# Adafruit_1_2in_7-segment.net
KiCad netlist of a schematic drawn in EAGLE
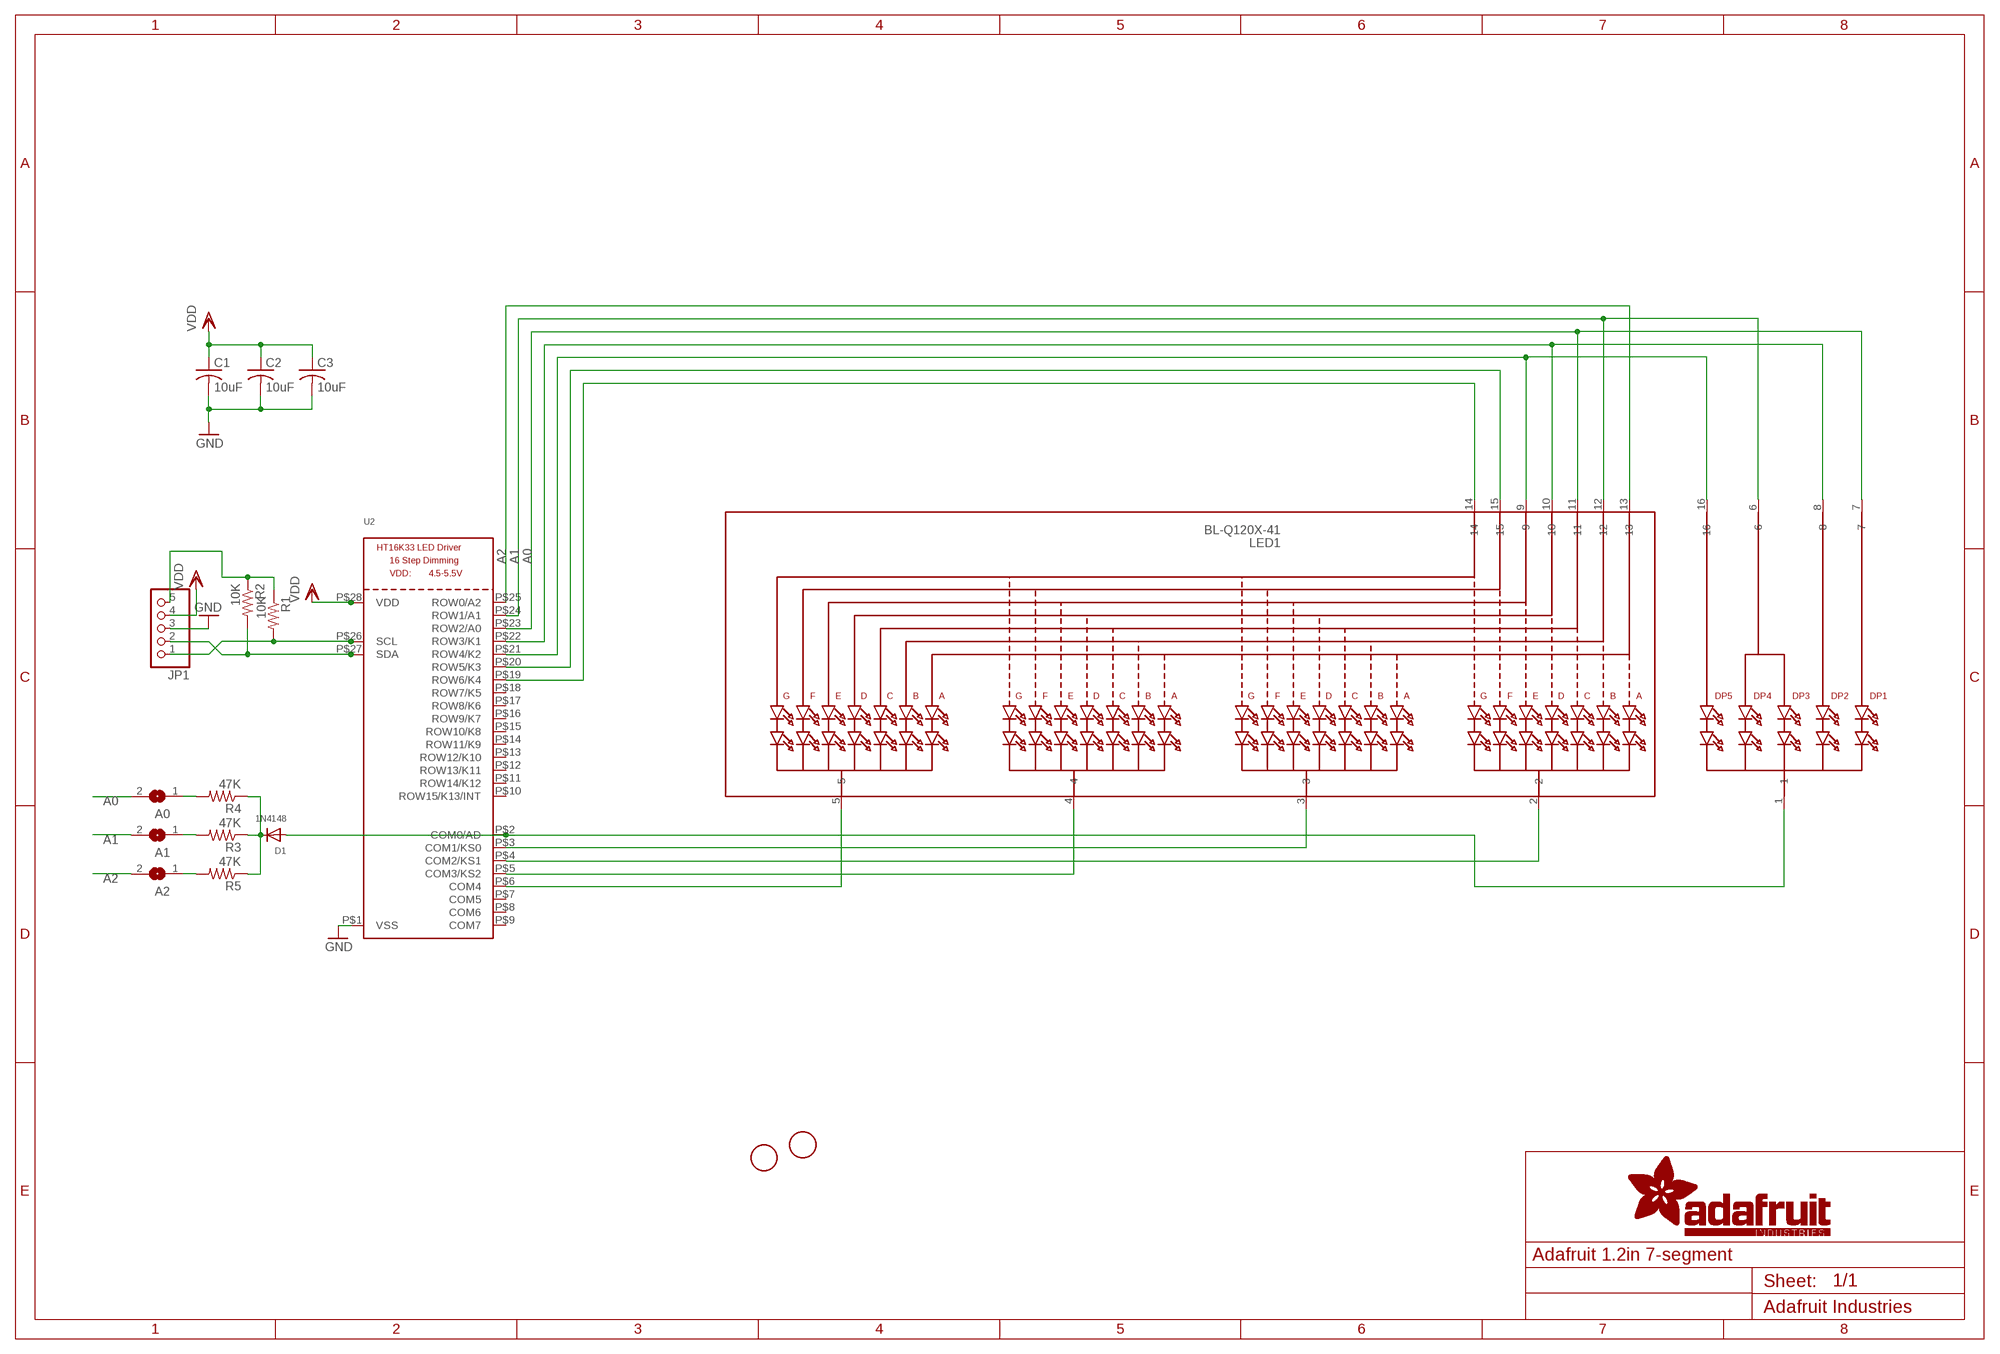
[diagram p0: schematic, sheet 1]

(export (version "E")
  (design (tool "Eeschema 10.0.6"))
  (components
    (comp (ref "A0")
      (value "SOLDERJUMPERREFLOW_NOPASTE")
      (footprint "eagle-import:SOLDERJUMPER_REFLOW_NOPASTE")
      (libsource (lib "eagle-import") (part "SOLDERJUMPERREFLOW_NOPASTE"))
    )
    (comp (ref "A1")
      (value "SOLDERJUMPERREFLOW_NOPASTE")
      (footprint "eagle-import:SOLDERJUMPER_REFLOW_NOPASTE")
      (libsource (lib "eagle-import") (part "SOLDERJUMPERREFLOW_NOPASTE"))
    )
    (comp (ref "A2")
      (value "SOLDERJUMPERREFLOW_NOPASTE")
      (footprint "eagle-import:SOLDERJUMPER_REFLOW_NOPASTE")
      (libsource (lib "eagle-import") (part "SOLDERJUMPERREFLOW_NOPASTE"))
    )
    (comp (ref "C1")
      (value "10uF")
      (footprint "eagle-import:C0805K")
      (libsource (lib "eagle-import") (part "C-USC0805K"))
    )
    (comp (ref "C2")
      (value "10uF")
      (footprint "eagle-import:C0805K")
      (libsource (lib "eagle-import") (part "C-USC0805K"))
    )
    (comp (ref "C3")
      (value "10uF")
      (footprint "eagle-import:C0805K")
      (libsource (lib "eagle-import") (part "C-USC0805K"))
    )
    (comp (ref "D1")
      (value "1N4148")
      (footprint "eagle-import:SOD-323F")
      (libsource (lib "eagle-import") (part "DIODESOD-323F"))
    )
    (comp (ref "JP1")
      (value "HEADER-1X576MIL")
      (footprint "eagle-import:1X05_ROUND_76")
      (libsource (lib "eagle-import") (part "HEADER-1X576MIL"))
    )
    (comp (ref "LED1")
      (value "BL-Q120X-41")
      (footprint "eagle-import:SEGMENT_BL-Q120A")
      (libsource (lib "eagle-import") (part "DISP_SEGMENT_4DIGIT_BL-Q120A"))
    )
    (comp (ref "R1")
      (value "10K")
      (footprint "eagle-import:R0805")
      (libsource (lib "eagle-import") (part "R-US_R0805"))
    )
    (comp (ref "R2")
      (value "10K")
      (footprint "eagle-import:R0805")
      (libsource (lib "eagle-import") (part "R-US_R0805"))
    )
    (comp (ref "R3")
      (value "47K")
      (footprint "eagle-import:R0805")
      (libsource (lib "eagle-import") (part "R-US_R0805"))
    )
    (comp (ref "R4")
      (value "47K")
      (footprint "eagle-import:R0805")
      (libsource (lib "eagle-import") (part "R-US_R0805"))
    )
    (comp (ref "R5")
      (value "47K")
      (footprint "eagle-import:R0805")
      (libsource (lib "eagle-import") (part "R-US_R0805"))
    )
    (comp (ref "U$1")
      (value "FIDUCIAL")
      (footprint "eagle-import:FIDUCIAL_1MM")
      (libsource (lib "eagle-import") (part "FIDUCIAL"))
    )
    (comp (ref "U$2")
      (value "FIDUCIAL")
      (footprint "eagle-import:FIDUCIAL_1MM")
      (libsource (lib "eagle-import") (part "FIDUCIAL"))
    )
    (comp (ref "U2")
      (value "HT16K33_SOP28")
      (footprint "eagle-import:SOP28_300MIL")
      (libsource (lib "eagle-import") (part "HT16K33_SOP28"))
    )
  )
  (nets
    (net (code "1") (name "/A0") (class "Default")
      (node (ref "A0") (pin "2") (pinfunction "2_2") (pintype "passive"))
      (node (ref "LED1") (pin "11") (pinfunction "11_11") (pintype "bidirectional"))
      (node (ref "LED1") (pin "7") (pinfunction "7_7") (pintype "bidirectional"))
      (node (ref "U2") (pin "P$23") (pinfunction "ROW2/A0_P$23") (pintype "bidirectional"))
    )
    (net (code "2") (name "/A1") (class "Default")
      (node (ref "A1") (pin "2") (pinfunction "2_2") (pintype "passive"))
      (node (ref "LED1") (pin "12") (pinfunction "12_12") (pintype "bidirectional"))
      (node (ref "LED1") (pin "6") (pinfunction "6_6") (pintype "bidirectional"))
      (node (ref "U2") (pin "P$24") (pinfunction "ROW1/A1_P$24") (pintype "bidirectional"))
    )
    (net (code "3") (name "/A2") (class "Default")
      (node (ref "A2") (pin "2") (pinfunction "2_2") (pintype "passive"))
      (node (ref "LED1") (pin "13") (pinfunction "13_13") (pintype "bidirectional"))
      (node (ref "U2") (pin "P$25") (pinfunction "ROW0/A2_P$25") (pintype "bidirectional"))
    )
    (net (code "4") (name "GND") (class "Default")
      (node (ref "C1") (pin "2") (pinfunction "2_2") (pintype "passive"))
      (node (ref "C2") (pin "2") (pinfunction "2_2") (pintype "passive"))
      (node (ref "C3") (pin "2") (pinfunction "2_2") (pintype "passive"))
      (node (ref "JP1") (pin "3") (pinfunction "3_3") (pintype "passive"))
      (node (ref "U2") (pin "P$1") (pinfunction "VSS_P$1") (pintype "bidirectional"))
    )
    (net (code "5") (name "Net-(A0-Pad1)") (class "Default")
      (node (ref "A0") (pin "1") (pinfunction "1_1") (pintype "passive"))
      (node (ref "R4") (pin "2") (pinfunction "2_2") (pintype "passive"))
    )
    (net (code "6") (name "Net-(A1-Pad1)") (class "Default")
      (node (ref "A1") (pin "1") (pinfunction "1_1") (pintype "passive"))
      (node (ref "R3") (pin "2") (pinfunction "2_2") (pintype "passive"))
    )
    (net (code "7") (name "Net-(A2-Pad1)") (class "Default")
      (node (ref "A2") (pin "1") (pinfunction "1_1") (pintype "passive"))
      (node (ref "R5") (pin "2") (pinfunction "2_2") (pintype "passive"))
    )
    (net (code "8") (name "Net-(D1-PadC)") (class "Default")
      (node (ref "D1") (pin "C") (pinfunction "C_C") (pintype "passive"))
      (node (ref "R3") (pin "1") (pinfunction "1_1") (pintype "passive"))
      (node (ref "R4") (pin "1") (pinfunction "1_1") (pintype "passive"))
      (node (ref "R5") (pin "1") (pinfunction "1_1") (pintype "passive"))
    )
    (net (code "9") (name "Net-(JP1-Pad5)") (class "Default")
      (node (ref "JP1") (pin "5") (pinfunction "5_5") (pintype "passive"))
      (node (ref "R1") (pin "1") (pinfunction "1_1") (pintype "passive"))
      (node (ref "R2") (pin "1") (pinfunction "1_1") (pintype "passive"))
    )
    (net (code "10") (name "Net-(U2-COM0{slash}AD)") (class "Default")
      (node (ref "D1") (pin "A") (pinfunction "A_A") (pintype "passive"))
      (node (ref "LED1") (pin "1") (pinfunction "1_1") (pintype "bidirectional"))
      (node (ref "U2") (pin "P$2") (pinfunction "COM0/AD_P$2") (pintype "bidirectional"))
    )
    (net (code "11") (name "Net-(U2-COM1{slash}KS0)") (class "Default")
      (node (ref "LED1") (pin "3") (pinfunction "3_3") (pintype "bidirectional"))
      (node (ref "U2") (pin "P$3") (pinfunction "COM1/KS0_P$3") (pintype "bidirectional"))
    )
    (net (code "12") (name "Net-(U2-COM2{slash}KS1)") (class "Default")
      (node (ref "LED1") (pin "2") (pinfunction "2_2") (pintype "bidirectional"))
      (node (ref "U2") (pin "P$4") (pinfunction "COM2/KS1_P$4") (pintype "bidirectional"))
    )
    (net (code "13") (name "Net-(U2-COM3{slash}KS2)") (class "Default")
      (node (ref "LED1") (pin "4") (pinfunction "4_4") (pintype "bidirectional"))
      (node (ref "U2") (pin "P$5") (pinfunction "COM3/KS2_P$5") (pintype "bidirectional"))
    )
    (net (code "14") (name "Net-(U2-COM4)") (class "Default")
      (node (ref "LED1") (pin "5") (pinfunction "5_5") (pintype "bidirectional"))
      (node (ref "U2") (pin "P$6") (pinfunction "COM4_P$6") (pintype "bidirectional"))
    )
    (net (code "15") (name "Net-(U2-ROW3{slash}K1)") (class "Default")
      (node (ref "LED1") (pin "10") (pinfunction "10_10") (pintype "bidirectional"))
      (node (ref "LED1") (pin "8") (pinfunction "8_8") (pintype "bidirectional"))
      (node (ref "U2") (pin "P$22") (pinfunction "ROW3/K1_P$22") (pintype "bidirectional"))
    )
    (net (code "16") (name "Net-(U2-ROW4{slash}K2)") (class "Default")
      (node (ref "LED1") (pin "16") (pinfunction "16_16") (pintype "bidirectional"))
      (node (ref "LED1") (pin "9") (pinfunction "9_9") (pintype "bidirectional"))
      (node (ref "U2") (pin "P$21") (pinfunction "ROW4/K2_P$21") (pintype "bidirectional"))
    )
    (net (code "17") (name "Net-(U2-ROW5{slash}K3)") (class "Default")
      (node (ref "LED1") (pin "15") (pinfunction "15_15") (pintype "bidirectional"))
      (node (ref "U2") (pin "P$20") (pinfunction "ROW5/K3_P$20") (pintype "bidirectional"))
    )
    (net (code "18") (name "Net-(U2-ROW6{slash}K4)") (class "Default")
      (node (ref "LED1") (pin "14") (pinfunction "14_14") (pintype "bidirectional"))
      (node (ref "U2") (pin "P$19") (pinfunction "ROW6/K4_P$19") (pintype "bidirectional"))
    )
    (net (code "19") (name "Net-(U2-SCL)") (class "Default")
      (node (ref "JP1") (pin "1") (pinfunction "1_1") (pintype "passive"))
      (node (ref "R1") (pin "2") (pinfunction "2_2") (pintype "passive"))
      (node (ref "U2") (pin "P$26") (pinfunction "SCL_P$26") (pintype "bidirectional"))
    )
    (net (code "20") (name "Net-(U2-SDA)") (class "Default")
      (node (ref "JP1") (pin "2") (pinfunction "2_2") (pintype "passive"))
      (node (ref "R2") (pin "2") (pinfunction "2_2") (pintype "passive"))
      (node (ref "U2") (pin "P$27") (pinfunction "SDA_P$27") (pintype "bidirectional"))
    )
    (net (code "21") (name "VDD") (class "Default")
      (node (ref "C1") (pin "1") (pinfunction "1_1") (pintype "passive"))
      (node (ref "C2") (pin "1") (pinfunction "1_1") (pintype "passive"))
      (node (ref "C3") (pin "1") (pinfunction "1_1") (pintype "passive"))
      (node (ref "JP1") (pin "4") (pinfunction "4_4") (pintype "passive"))
      (node (ref "U2") (pin "P$28") (pinfunction "VDD_P$28") (pintype "bidirectional"))
    )
    (net (code "22") (name "unconnected-(U2-COM5-PadP$7)") (class "Default")
      (node (ref "U2") (pin "P$7") (pinfunction "COM5_P$7") (pintype "bidirectional"))
    )
    (net (code "23") (name "unconnected-(U2-COM6-PadP$8)") (class "Default")
      (node (ref "U2") (pin "P$8") (pinfunction "COM6_P$8") (pintype "bidirectional"))
    )
    (net (code "24") (name "unconnected-(U2-COM7-PadP$9)") (class "Default")
      (node (ref "U2") (pin "P$9") (pinfunction "COM7_P$9") (pintype "bidirectional"))
    )
    (net (code "25") (name "unconnected-(U2-ROW7{slash}K5-PadP$18)") (class "Default")
      (node (ref "U2") (pin "P$18") (pinfunction "ROW7/K5_P$18") (pintype "bidirectional"))
    )
    (net (code "26") (name "unconnected-(U2-ROW8{slash}K6-PadP$17)") (class "Default")
      (node (ref "U2") (pin "P$17") (pinfunction "ROW8/K6_P$17") (pintype "bidirectional"))
    )
    (net (code "27") (name "unconnected-(U2-ROW9{slash}K7-PadP$16)") (class "Default")
      (node (ref "U2") (pin "P$16") (pinfunction "ROW9/K7_P$16") (pintype "bidirectional"))
    )
    (net (code "28") (name "unconnected-(U2-ROW10{slash}K8-PadP$15)") (class "Default")
      (node (ref "U2") (pin "P$15") (pinfunction "ROW10/K8_P$15") (pintype "bidirectional"))
    )
    (net (code "29") (name "unconnected-(U2-ROW11{slash}K9-PadP$14)") (class "Default")
      (node (ref "U2") (pin "P$14") (pinfunction "ROW11/K9_P$14") (pintype "bidirectional"))
    )
    (net (code "30") (name "unconnected-(U2-ROW12{slash}K10-PadP$13)") (class "Default")
      (node (ref "U2") (pin "P$13") (pinfunction "ROW12/K10_P$13") (pintype "bidirectional"))
    )
    (net (code "31") (name "unconnected-(U2-ROW13{slash}K11-PadP$12)") (class "Default")
      (node (ref "U2") (pin "P$12") (pinfunction "ROW13/K11_P$12") (pintype "bidirectional"))
    )
    (net (code "32") (name "unconnected-(U2-ROW14{slash}K12-PadP$11)") (class "Default")
      (node (ref "U2") (pin "P$11") (pinfunction "ROW14/K12_P$11") (pintype "bidirectional"))
    )
    (net (code "33") (name "unconnected-(U2-ROW15{slash}K13{slash}INT-PadP$10)") (class "Default")
      (node (ref "U2") (pin "P$10") (pinfunction "ROW15/K13/INT_P$10") (pintype "bidirectional"))
    )
  )
)
